# Sheet1.net
KiCad netlist of a schematic drawn in Altium Designer
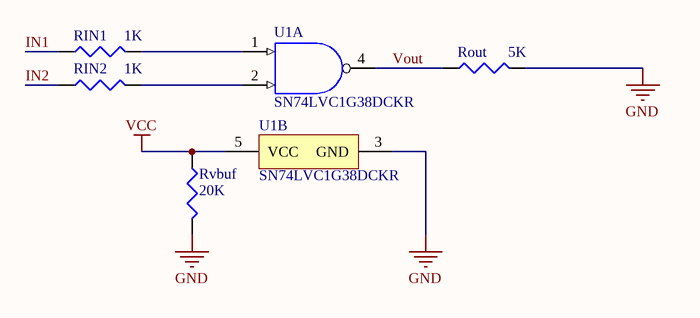
[diagram p0: Sheet1.SchDoc]

(export (version "E")
  (design (tool "Eeschema 10.0.6"))
  (components
    (comp (ref "RIN1")
      (value "1K")
      (footprint "J1-0603")
      (description "Resistor")
      (fields (field (name "Comment") "Res3") (field (name "PUBLISHER") "Altium Limited"))
      (libsource (lib "Miscellaneous Devices") (part "Res3"))
    )
    (comp (ref "RIN2")
      (value "1K")
      (footprint "J1-0603")
      (description "Resistor")
      (fields (field (name "Comment") "Res3") (field (name "PUBLISHER") "Altium Limited"))
      (libsource (lib "Miscellaneous Devices") (part "Res3"))
    )
    (comp (ref "Rout")
      (value "5K")
      (footprint "J1-0603")
      (description "Resistor")
      (fields (field (name "Comment") "Res3") (field (name "PUBLISHER") "Altium Limited"))
      (libsource (lib "Miscellaneous Devices") (part "Res3"))
    )
    (comp (ref "Rvbuf")
      (value "20K")
      (footprint "J1-0603")
      (description "Resistor")
      (fields (field (name "Comment") "Res3") (field (name "PUBLISHER") "Altium Limited"))
      (libsource (lib "Miscellaneous Devices") (part "Res3"))
    )
    (comp (ref "U1")
      (value "SN74LVC1G38DCKR")
      (footprint "DCK0005A_L")
      (description "Single 2-Input NAND Gate with Open Drain Output, DCK0005A, LARGE T&R")
      (fields
        (field (name "MANUFACTURER") "Texas Instruments")
        (field (name "GENERIC PART NUMBER") "SN74LVC1G38")
      )
      (libsource (lib "altium-import") (part "root_0_TI-SN74LVC1G38-5_"))
    )
  )
  (nets
    (net (code "1") (name "/IN1") (class "Default")
      (node (ref "RIN1") (pin "1") (pinfunction "1_1") (pintype "passive"))
    )
    (net (code "2") (name "/IN2") (class "Default")
      (node (ref "RIN2") (pin "1") (pinfunction "1_1") (pintype "passive"))
    )
    (net (code "3") (name "/Vout") (class "Default")
      (node (ref "Rout") (pin "1") (pinfunction "1_1") (pintype "passive"))
      (node (ref "U1") (pin "4") (pinfunction "Y_4") (pintype "open_collector"))
    )
    (net (code "4") (name "GND") (class "Default")
      (node (ref "Rout") (pin "2") (pinfunction "2_2") (pintype "passive"))
      (node (ref "Rvbuf") (pin "2") (pinfunction "2_2") (pintype "passive"))
      (node (ref "U1") (pin "3") (pinfunction "GND_3") (pintype "power_in"))
    )
    (net (code "5") (name "Net-(U1A-A)") (class "Default")
      (node (ref "RIN1") (pin "2") (pinfunction "2_2") (pintype "passive"))
      (node (ref "U1") (pin "1") (pinfunction "A_1") (pintype "input"))
    )
    (net (code "6") (name "Net-(U1A-B)") (class "Default")
      (node (ref "RIN2") (pin "2") (pinfunction "2_2") (pintype "passive"))
      (node (ref "U1") (pin "2") (pinfunction "B_2") (pintype "input"))
    )
    (net (code "7") (name "VCC") (class "Default")
      (node (ref "Rvbuf") (pin "1") (pinfunction "1_1") (pintype "passive"))
      (node (ref "U1") (pin "5") (pinfunction "VCC_5") (pintype "power_in"))
    )
  )
)
